# blinky_ver1.net
KiCad netlist of a schematic drawn in EAGLE
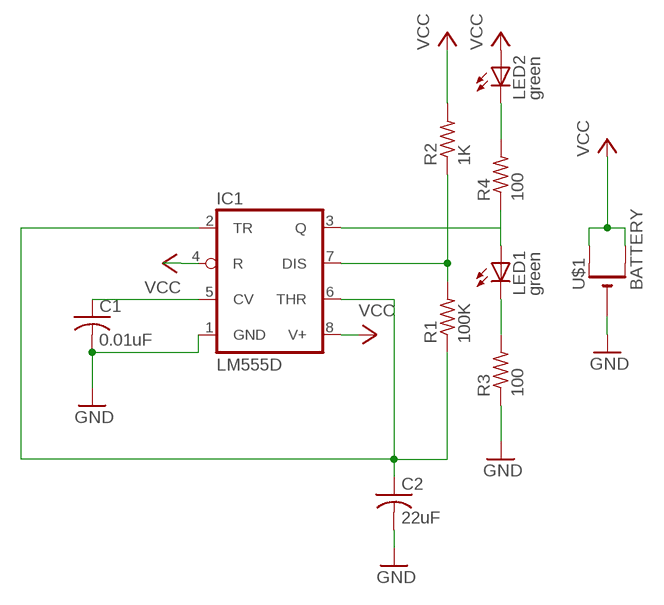
[diagram p0: schematic, sheet 1]

(export (version "E")
  (design (tool "Eeschema 10.0.6"))
  (components
    (comp (ref "C1")
      (value "0.01uF")
      (footprint "eagle-import:C0805")
      (libsource (lib "eagle-import") (part "C-USC0805"))
    )
    (comp (ref "C2")
      (value "22uF")
      (footprint "eagle-import:C0805")
      (libsource (lib "eagle-import") (part "C-USC0805"))
    )
    (comp (ref "IC1")
      (value "LM555D")
      (footprint "eagle-import:SO08")
      (libsource (lib "eagle-import") (part "555DLM"))
    )
    (comp (ref "LED1")
      (value "green")
      (footprint "eagle-import:CHIPLED_0805")
      (libsource (lib "eagle-import") (part "LEDCHIPLED_0805"))
    )
    (comp (ref "LED2")
      (value "green")
      (footprint "eagle-import:CHIPLED_0805")
      (libsource (lib "eagle-import") (part "LEDCHIPLED_0805"))
    )
    (comp (ref "R1")
      (value "100K")
      (footprint "eagle-import:R0805")
      (libsource (lib "eagle-import") (part "R-US_R0805"))
    )
    (comp (ref "R2")
      (value "1K")
      (footprint "eagle-import:R0805")
      (libsource (lib "eagle-import") (part "R-US_R0805"))
    )
    (comp (ref "R3")
      (value "100")
      (footprint "eagle-import:R0805")
      (libsource (lib "eagle-import") (part "R-US_R0805"))
    )
    (comp (ref "R4")
      (value "100")
      (footprint "eagle-import:R0805")
      (libsource (lib "eagle-import") (part "R-US_R0805"))
    )
    (comp (ref "U$1")
      (value "BATTERY")
      (footprint "eagle-import:CR1220-SMD")
      (libsource (lib "eagle-import") (part "CR1220SMT"))
    )
  )
  (nets
    (net (code "1") (name "GND") (class "Default")
      (node (ref "C1") (pin "2") (pinfunction "2_2") (pintype "passive"))
      (node (ref "C2") (pin "2") (pinfunction "2_2") (pintype "passive"))
      (node (ref "IC1") (pin "1") (pinfunction "GND_1") (pintype "power_in"))
      (node (ref "R3") (pin "1") (pinfunction "1_1") (pintype "passive"))
      (node (ref "U$1") (pin "-") (pinfunction "-_-") (pintype "passive"))
    )
    (net (code "2") (name "Net-(IC1-CV)") (class "Default")
      (node (ref "C1") (pin "1") (pinfunction "1_1") (pintype "passive"))
      (node (ref "IC1") (pin "5") (pinfunction "CV_5") (pintype "input"))
    )
    (net (code "3") (name "Net-(IC1-DIS)") (class "Default")
      (node (ref "IC1") (pin "7") (pinfunction "DIS_7") (pintype "input"))
      (node (ref "R1") (pin "2") (pinfunction "2_2") (pintype "passive"))
      (node (ref "R2") (pin "1") (pinfunction "1_1") (pintype "passive"))
    )
    (net (code "4") (name "Net-(IC1-Q)") (class "Default")
      (node (ref "IC1") (pin "3") (pinfunction "Q_3") (pintype "output"))
      (node (ref "LED1") (pin "A") (pinfunction "A_A") (pintype "passive"))
      (node (ref "R4") (pin "1") (pinfunction "1_1") (pintype "passive"))
    )
    (net (code "5") (name "Net-(IC1-THR)") (class "Default")
      (node (ref "C2") (pin "1") (pinfunction "1_1") (pintype "passive"))
      (node (ref "IC1") (pin "2") (pinfunction "TR_2") (pintype "input"))
      (node (ref "IC1") (pin "6") (pinfunction "THR_6") (pintype "input"))
      (node (ref "R1") (pin "1") (pinfunction "1_1") (pintype "passive"))
    )
    (net (code "6") (name "Net-(LED1-PadC)") (class "Default")
      (node (ref "LED1") (pin "C") (pinfunction "C_C") (pintype "passive"))
      (node (ref "R3") (pin "2") (pinfunction "2_2") (pintype "passive"))
    )
    (net (code "7") (name "Net-(LED2-PadC)") (class "Default")
      (node (ref "LED2") (pin "C") (pinfunction "C_C") (pintype "passive"))
      (node (ref "R4") (pin "2") (pinfunction "2_2") (pintype "passive"))
    )
    (net (code "8") (name "VCC") (class "Default")
      (node (ref "IC1") (pin "4") (pinfunction "R_4") (pintype "input"))
      (node (ref "IC1") (pin "8") (pinfunction "V+_8") (pintype "power_in"))
      (node (ref "LED2") (pin "A") (pinfunction "A_A") (pintype "passive"))
      (node (ref "R2") (pin "2") (pinfunction "2_2") (pintype "passive"))
      (node (ref "U$1") (pin "+$1") (pinfunction "+_+$1") (pintype "passive"))
      (node (ref "U$1") (pin "+$2") (pinfunction "+1_+$2") (pintype "passive"))
    )
  )
)
